# Protection_channel_D_Page_5.net
KiCad netlist of a schematic drawn in Altium Designer
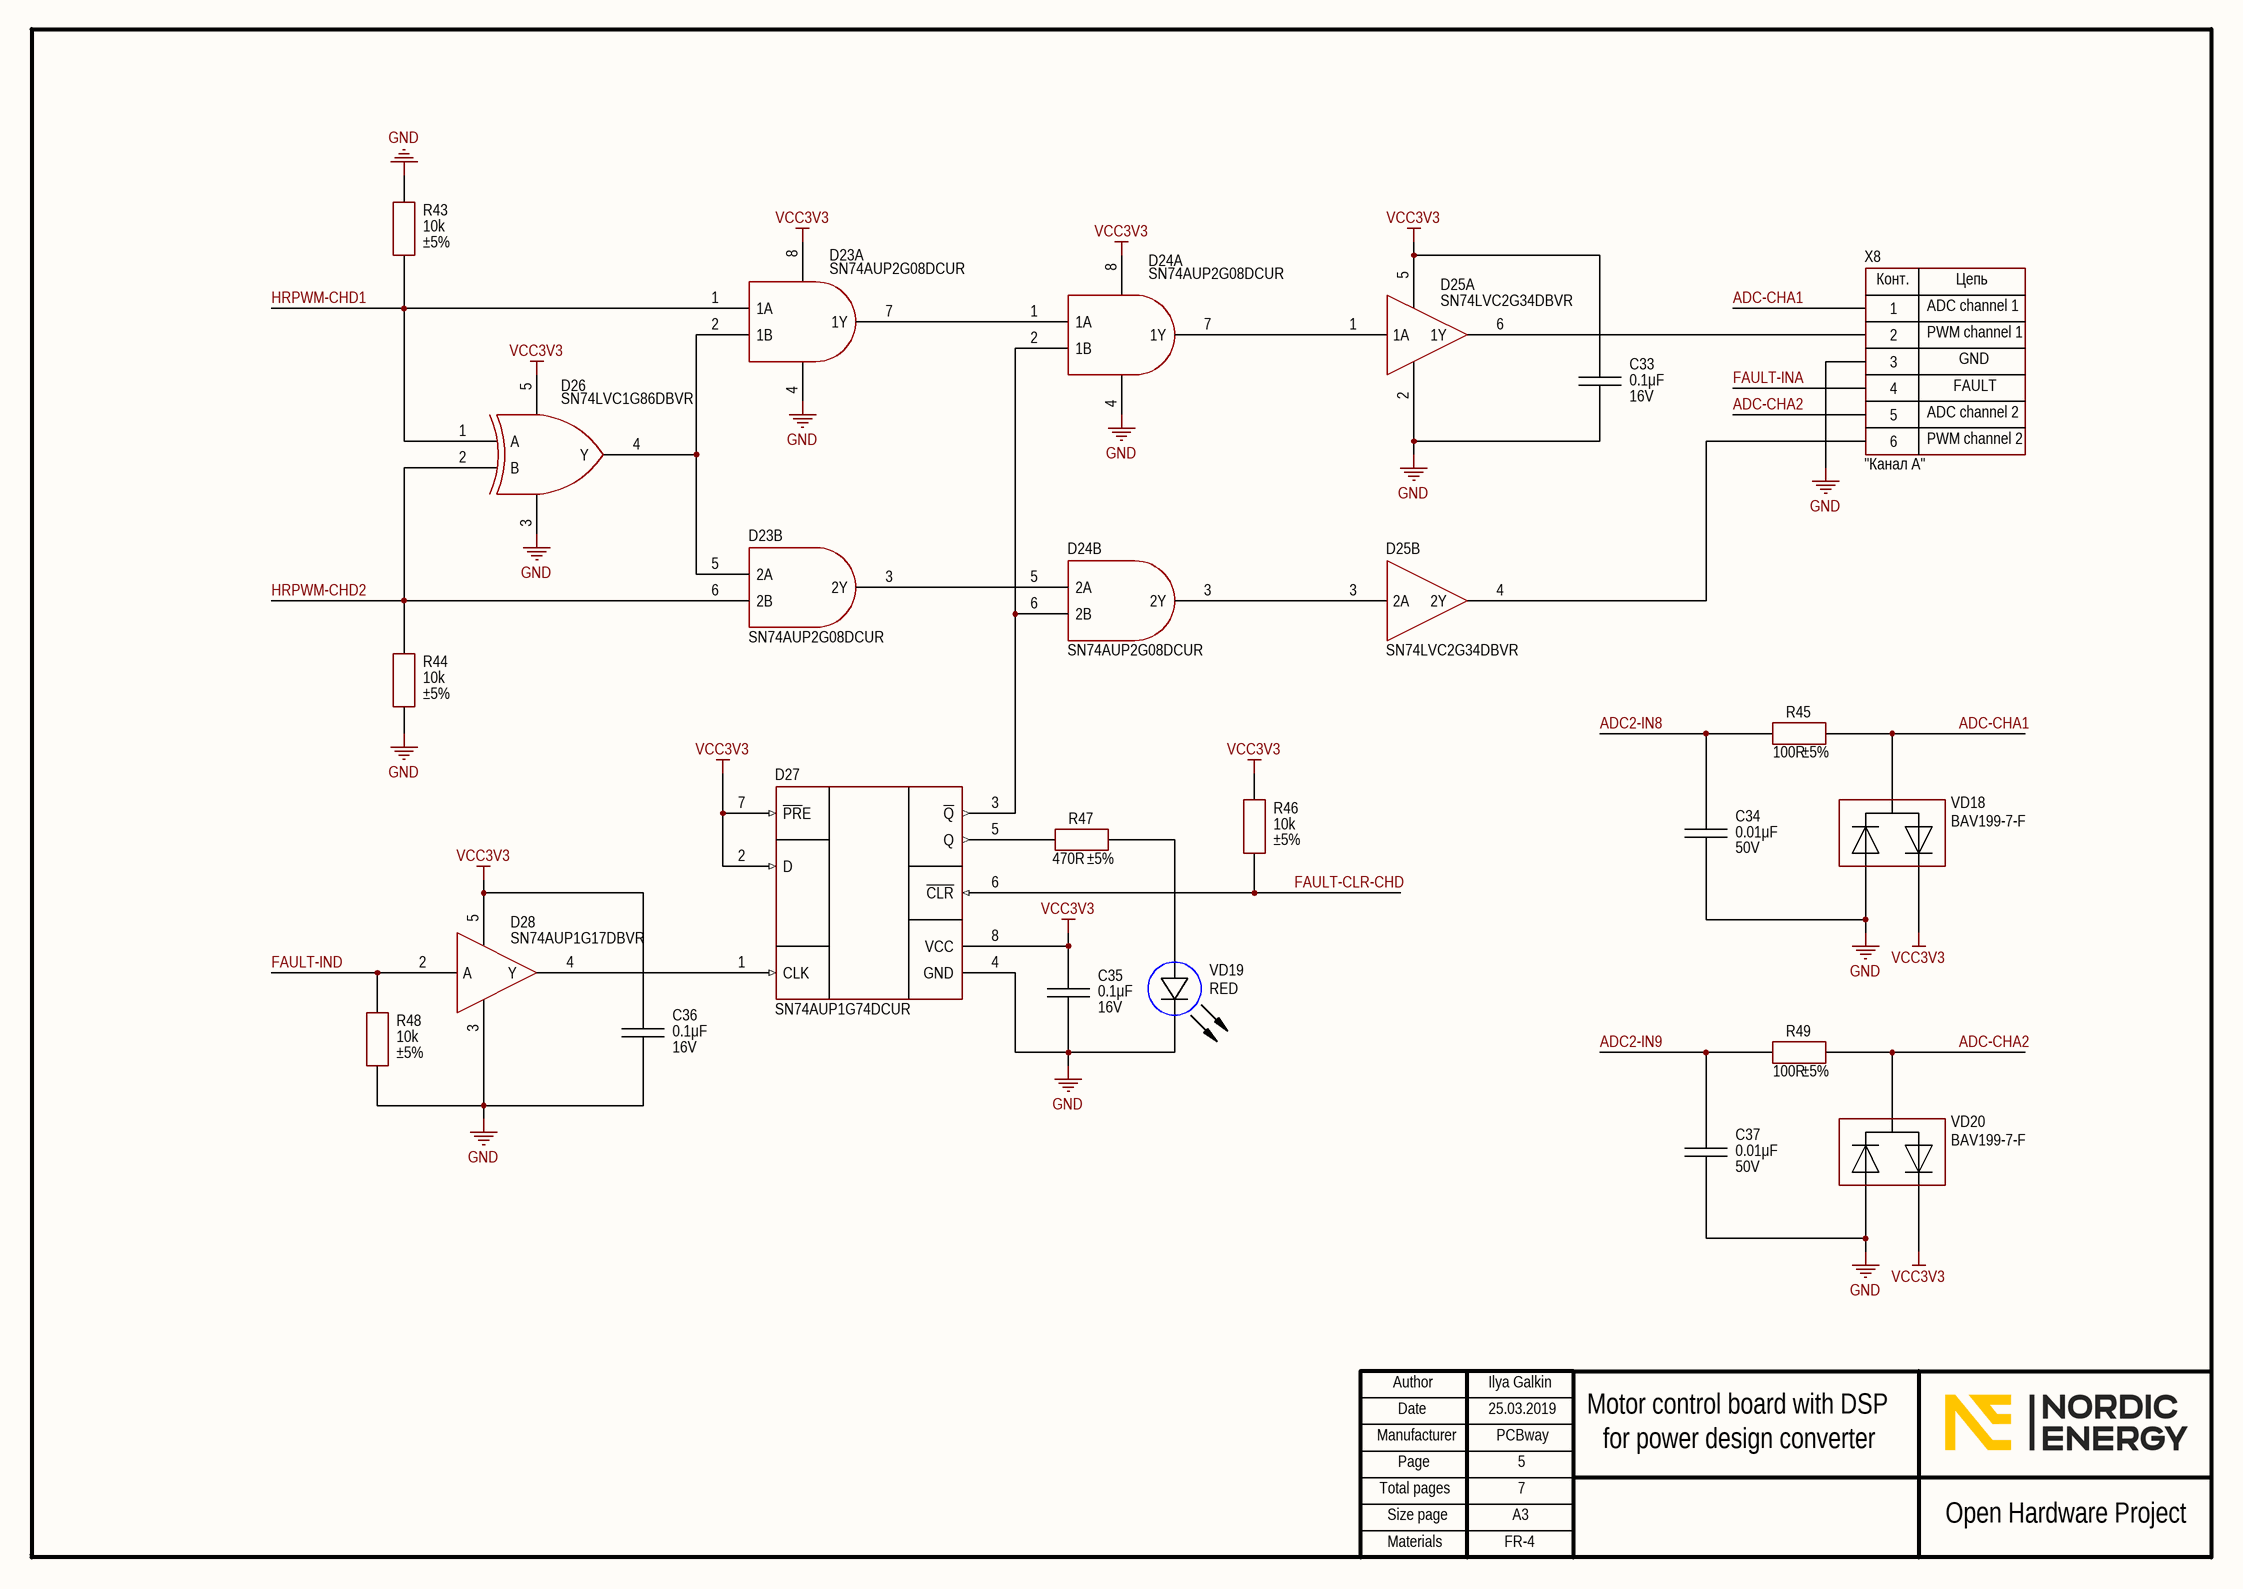
[diagram p0: Protection channel D. Page 5.SchDoc]

(export (version "E")
  (design (tool "Eeschema 10.0.6"))
  (components
    (comp (ref "C33")
      (value "0.1μF")
      (footprint "CAP: 0805")
      (fields
        (field (name "MANUFACTURER") "Yageo")
        (field (name "PARTNUMBER") "CC0805KRX7R7BB104")
        (field (name "VALUEMANUFACTURERPARTNUMBER") "Ceramic capacitor, 0.1μF, X7R, ±10%, 16V, 0805, -55...+125°C")
        (field (name "VOLTAGE") "16V")
      )
      (libsource (lib "Capacitor") (part "Ceramic_0805"))
    )
    (comp (ref "C34")
      (value "0.01μF")
      (footprint "CAP: 0805")
      (fields
        (field (name "MANUFACTURER") "Yageo")
        (field (name "PARTNUMBER") "CC0805KRX7R9BB103")
        (field (name "VALUEMANUFACTURERPARTNUMBER") "Ceramic capacitor, 0.01μF, X7R, ±10%, 50V, 0805, -55...+125°C")
        (field (name "VOLTAGE") "50V")
      )
      (libsource (lib "Capacitor") (part "Ceramic_0805"))
    )
    (comp (ref "C35")
      (value "0.1μF")
      (footprint "CAP: 0805")
      (fields
        (field (name "MANUFACTURER") "Yageo")
        (field (name "PARTNUMBER") "CC0805KRX7R7BB104")
        (field (name "VALUEMANUFACTURERPARTNUMBER") "Ceramic capacitor, 0.1μF, X7R, ±10%, 16V, 0805, -55...+125°C")
        (field (name "VOLTAGE") "16V")
      )
      (libsource (lib "Capacitor") (part "Ceramic_0805"))
    )
    (comp (ref "C36")
      (value "0.1μF")
      (footprint "CAP: 0805")
      (fields
        (field (name "MANUFACTURER") "Yageo")
        (field (name "PARTNUMBER") "CC0805KRX7R7BB104")
        (field (name "VALUEMANUFACTURERPARTNUMBER") "Ceramic capacitor, 0.1μF, X7R, ±10%, 16V, 0805, -55...+125°C")
        (field (name "VOLTAGE") "16V")
      )
      (libsource (lib "Capacitor") (part "Ceramic_0805"))
    )
    (comp (ref "C37")
      (value "0.01μF")
      (footprint "CAP: 0805")
      (fields
        (field (name "MANUFACTURER") "Yageo")
        (field (name "PARTNUMBER") "CC0805KRX7R9BB103")
        (field (name "VALUEMANUFACTURERPARTNUMBER") "Ceramic capacitor, 0.01μF, X7R, ±10%, 50V, 0805, -55...+125°C")
        (field (name "VOLTAGE") "50V")
      )
      (libsource (lib "Capacitor") (part "Ceramic_0805"))
    )
    (comp (ref "D23")
      (value "~")
      (footprint "8-VSSOP")
      (description "AND")
      (fields
        (field (name "MANUFACTURER") "Texas Instruments")
        (field (name "VALUEMANUFACTURERPARTNUMBER") "IC logic AND, 0.8...3.6V, -40...+855°C, 8-VSSOP")
        (field (name "PARTNUMBER") "SN74AUP2G08DCUR")
      )
      (libsource (lib "IC. Logic") (part "SN74AUP2G08DCUR"))
    )
    (comp (ref "D24")
      (value "~")
      (footprint "8-VSSOP")
      (description "AND")
      (fields
        (field (name "MANUFACTURER") "Texas Instruments")
        (field (name "VALUEMANUFACTURERPARTNUMBER") "IC logic AND, 0.8...3.6V, -40...+855°C, 8-VSSOP")
        (field (name "PARTNUMBER") "SN74AUP2G08DCUR")
      )
      (libsource (lib "IC. Logic") (part "SN74AUP2G08DCUR"))
    )
    (comp (ref "D25")
      (value "~")
      (footprint "SOT23-6")
      (description "Buffer")
      (fields
        (field (name "MANUFACTURER") "Texas Instruments")
        (field (name "VALUEMANUFACTURERPARTNUMBER") "IC logic buffer, 1.65...5.5V, -40...+125°C, SOT23-6")
        (field (name "PARTNUMBER") "SN74LVC2G34DBVR")
      )
      (libsource (lib "IC. Logic") (part "SN74LVC2G34DBVR"))
    )
    (comp (ref "D26")
      (value "~")
      (footprint "SOT23-5")
      (description "XOR")
      (fields
        (field (name "MANUFACTURER") "Texas Instruments")
        (field (name "VALUEMANUFACTURERPARTNUMBER") "IC logic XOR, 1.65...5.5V, -40...+125°C, SOT23-5")
        (field (name "PARTNUMBER") "SN74LVC1G86DBVR")
      )
      (libsource (lib "IC. Logic") (part "SN74LVC1G86DBVR"))
    )
    (comp (ref "D27")
      (value "~")
      (footprint "8-VSSOP")
      (description "D-trigger")
      (fields
        (field (name "MANUFACTURER") "Texas Instruments")
        (field (name "VALUEMANUFACTURERPARTNUMBER") "ICtrigger D-type, 0.8...3.6V, -40...+85°C, 8-VSSOP")
        (field (name "PARTNUMBER") "SN74AUP1G74DCUR")
      )
      (libsource (lib "IC. Logic") (part "SN74AUP1G74DCUR"))
    )
    (comp (ref "D28")
      (value "~")
      (footprint "SOT23-5")
      (description "Schmitt trigger")
      (fields
        (field (name "MANUFACTURER") "Texas Instruments")
        (field (name "VALUEMANUFACTURERPARTNUMBER") "IC Schmitt trigger, 0.8...3.6V, -40...+85°C, SOT23-6")
        (field (name "PARTNUMBER") "SN74AUP1G17DBVR")
      )
      (libsource (lib "IC. Logic") (part "SN74AUP1G17DBVR"))
    )
    (comp (ref "R43")
      (value "10k")
      (footprint "RES: 0805")
      (fields
        (field (name "MANUFACTURER") "Yageo")
        (field (name "PARTNUMBER") "RC0805JR-0710KL")
        (field (name "VALUEMANUFACTURERPARTNUMBER") "Resistor film, 10k, ±5%, 0805, 0.125W, -55...+125°C")
        (field (name "TOLERANCE") "±5%")
      )
      (libsource (lib "Resistor") (part "Resistor_0805"))
    )
    (comp (ref "R44")
      (value "10k")
      (footprint "RES: 0805")
      (fields
        (field (name "MANUFACTURER") "Yageo")
        (field (name "PARTNUMBER") "RC0805JR-0710KL")
        (field (name "VALUEMANUFACTURERPARTNUMBER") "Resistor film, 10k, ±5%, 0805, 0.125W, -55...+125°C")
        (field (name "TOLERANCE") "±5%")
      )
      (libsource (lib "Resistor") (part "Resistor_0805"))
    )
    (comp (ref "R45")
      (value "100R")
      (footprint "RES: 0805")
      (fields
        (field (name "MANUFACTURER") "Yageo")
        (field (name "PARTNUMBER") "RC0805JR-07100RL")
        (field (name "VALUEMANUFACTURERPARTNUMBER") "Resistor film, 100R, ±5%, 0805, 0.125W, -55...+125°C")
        (field (name "TOLERANCE") "±5%")
      )
      (libsource (lib "") (part "Resistor_0805_1"))
    )
    (comp (ref "R46")
      (value "10k")
      (footprint "RES: 0805")
      (fields
        (field (name "MANUFACTURER") "Yageo")
        (field (name "PARTNUMBER") "RC0805JR-0710KL")
        (field (name "VALUEMANUFACTURERPARTNUMBER") "Resistor film, 10k, ±5%, 0805, 0.125W, -55...+125°C")
        (field (name "TOLERANCE") "±5%")
      )
      (libsource (lib "Resistor") (part "Resistor_0805"))
    )
    (comp (ref "R47")
      (value "470R")
      (footprint "RES: 0805")
      (fields
        (field (name "MANUFACTURER") "Yageo")
        (field (name "PARTNUMBER") "RC0805JR-07470RL")
        (field (name "VALUEMANUFACTURERPARTNUMBER") "Resistor film, 470R, ±5%, 0805, 0.125W, -55...+125°C")
        (field (name "TOLERANCE") "±5%")
      )
      (libsource (lib "") (part "Resistor_0805_2"))
    )
    (comp (ref "R48")
      (value "10k")
      (footprint "RES: 0805")
      (fields
        (field (name "MANUFACTURER") "Yageo")
        (field (name "PARTNUMBER") "RC0805JR-0710KL")
        (field (name "VALUEMANUFACTURERPARTNUMBER") "Resistor film, 10k, ±5%, 0805, 0.125W, -55...+125°C")
        (field (name "TOLERANCE") "±5%")
      )
      (libsource (lib "Resistor") (part "Resistor_0805"))
    )
    (comp (ref "R49")
      (value "100R")
      (footprint "RES: 0805")
      (fields
        (field (name "MANUFACTURER") "Yageo")
        (field (name "PARTNUMBER") "RC0805JR-07100RL")
        (field (name "VALUEMANUFACTURERPARTNUMBER") "Resistor film, 100R, ±5%, 0805, 0.125W, -55...+125°C")
        (field (name "TOLERANCE") "±5%")
      )
      (libsource (lib "") (part "Resistor_0805_1"))
    )
    (comp (ref "VD18")
      (value "~")
      (footprint "SOT23")
      (fields
        (field (name "MANUFACTURER") "Diodes Incorporated")
        (field (name "VALUEMANUFACTURERPARTNUMBER") "Diode array, 85V, 140mA, 1.1V, 3us, SOT-23, -65...+150°C")
        (field (name "VOLTAGE") "85V")
        (field (name "PARTNUMBER") "BAV199-7-F")
      )
      (libsource (lib "Diode") (part "Diode_array"))
    )
    (comp (ref "VD19")
      (value "~")
      (footprint "LED: 0805R")
      (fields
        (field (name "MANUFACTURER") "Wurth")
        (field (name "VALUEMANUFACTURERPARTNUMBER") "LED, 20mA, 2V, 0805, -55...+150°C")
        (field (name "PARTNUMBER") "150080RS75000")
        (field (name "COLOR") "RED")
      )
      (libsource (lib "Diode") (part "LED_single"))
    )
    (comp (ref "VD20")
      (value "~")
      (footprint "SOT23")
      (fields
        (field (name "MANUFACTURER") "Diodes Incorporated")
        (field (name "VALUEMANUFACTURERPARTNUMBER") "Diode array, 85V, 140mA, 1.1V, 3us, SOT-23, -65...+150°C")
        (field (name "VOLTAGE") "85V")
        (field (name "PARTNUMBER") "BAV199-7-F")
      )
      (libsource (lib "Diode") (part "Diode_array"))
    )
    (comp (ref "X8")
      (value "~")
      (footprint "CON: PLD-6")
      (fields
        (field (name "MANUFACTURER") "Connfly")
        (field (name "VALUEMANUFACTURERPARTNUMBER") "Connector, 6pin, 2.54mm, 500VAC, 3A")
        (field (name "PARTNUMBER") "PLD-6")
        (field (name "COMMENTTEXT") "\"Канал А\"")
      )
      (libsource (lib "Connector") (part "PLD-6"))
    )
  )
  (nets
    (net (code "1") (name "/ADC-CHA1") (class "Default")
      (node (ref "R45") (pin "2") (pinfunction "2_2") (pintype "passive"))
      (node (ref "VD18") (pin "3") (pinfunction "3_3") (pintype "passive"))
      (node (ref "X8") (pin "1") (pinfunction "1_1") (pintype "passive"))
    )
    (net (code "2") (name "/ADC-CHA2") (class "Default")
      (node (ref "R49") (pin "2") (pinfunction "2_2") (pintype "passive"))
      (node (ref "VD20") (pin "3") (pinfunction "3_3") (pintype "passive"))
      (node (ref "X8") (pin "5") (pinfunction "5_5") (pintype "power_in"))
    )
    (net (code "3") (name "/ADC2-IN8") (class "Default")
      (node (ref "C34") (pin "2") (pinfunction "2_2") (pintype "power_in"))
      (node (ref "R45") (pin "1") (pinfunction "1_1") (pintype "passive"))
    )
    (net (code "4") (name "/ADC2-IN9") (class "Default")
      (node (ref "C37") (pin "2") (pinfunction "2_2") (pintype "power_in"))
      (node (ref "R49") (pin "1") (pinfunction "1_1") (pintype "passive"))
    )
    (net (code "5") (name "/FAULT-CLR-CHD") (class "Default")
      (node (ref "D27") (pin "6") (pinfunction "~{CLR}_6") (pintype "input"))
      (node (ref "R46") (pin "2") (pinfunction "2_2") (pintype "passive"))
    )
    (net (code "6") (name "/FAULT-INA") (class "Default")
      (node (ref "X8") (pin "4") (pinfunction "4_4") (pintype "power_in"))
    )
    (net (code "7") (name "/FAULT-IND") (class "Default")
      (node (ref "D28") (pin "2") (pinfunction "A_2") (pintype "passive"))
      (node (ref "R48") (pin "1") (pinfunction "1_1") (pintype "passive"))
    )
    (net (code "8") (name "/HRPWM-CHD1") (class "Default")
      (node (ref "D23") (pin "1") (pinfunction "1A_1") (pintype "passive"))
      (node (ref "D26") (pin "1") (pinfunction "A_1") (pintype "passive"))
      (node (ref "R43") (pin "2") (pinfunction "2_2") (pintype "passive"))
    )
    (net (code "9") (name "/HRPWM-CHD2") (class "Default")
      (node (ref "D23") (pin "6") (pinfunction "2B_6") (pintype "passive"))
      (node (ref "D26") (pin "2") (pinfunction "B_2") (pintype "passive"))
      (node (ref "R44") (pin "1") (pinfunction "1_1") (pintype "passive"))
    )
    (net (code "10") (name "GND") (class "Default")
      (node (ref "C33") (pin "1") (pinfunction "1_1") (pintype "power_in"))
      (node (ref "C34") (pin "1") (pinfunction "1_1") (pintype "power_in"))
      (node (ref "C35") (pin "1") (pinfunction "1_1") (pintype "power_in"))
      (node (ref "C36") (pin "1") (pinfunction "1_1") (pintype "power_in"))
      (node (ref "C37") (pin "1") (pinfunction "1_1") (pintype "power_in"))
      (node (ref "D23") (pin "4") (pintype "passive"))
      (node (ref "D24") (pin "4") (pintype "passive"))
      (node (ref "D25") (pin "2") (pintype "passive"))
      (node (ref "D26") (pin "3") (pintype "passive"))
      (node (ref "D27") (pin "4") (pinfunction "GND_4") (pintype "passive"))
      (node (ref "D28") (pin "3") (pintype "passive"))
      (node (ref "R43") (pin "1") (pinfunction "1_1") (pintype "passive"))
      (node (ref "R44") (pin "2") (pinfunction "2_2") (pintype "passive"))
      (node (ref "R48") (pin "2") (pinfunction "2_2") (pintype "passive"))
      (node (ref "VD18") (pin "1") (pinfunction "1_1") (pintype "passive"))
      (node (ref "VD19") (pin "2") (pinfunction "C_2") (pintype "passive"))
      (node (ref "VD20") (pin "1") (pinfunction "1_1") (pintype "passive"))
      (node (ref "X8") (pin "3") (pinfunction "3_3") (pintype "power_in"))
    )
    (net (code "11") (name "Net-(D23A-1B)") (class "Default")
      (node (ref "D23") (pin "2") (pinfunction "1B_2") (pintype "passive"))
      (node (ref "D23") (pin "5") (pinfunction "2A_5") (pintype "passive"))
      (node (ref "D26") (pin "4") (pinfunction "Y_4") (pintype "passive"))
    )
    (net (code "12") (name "Net-(D23A-1Y)") (class "Default")
      (node (ref "D23") (pin "7") (pinfunction "1Y_7") (pintype "passive"))
      (node (ref "D24") (pin "1") (pinfunction "1A_1") (pintype "passive"))
    )
    (net (code "13") (name "Net-(D23B-2Y)") (class "Default")
      (node (ref "D23") (pin "3") (pinfunction "2Y_3") (pintype "passive"))
      (node (ref "D24") (pin "5") (pinfunction "2A_5") (pintype "passive"))
    )
    (net (code "14") (name "Net-(D24A-1B)") (class "Default")
      (node (ref "D24") (pin "2") (pinfunction "1B_2") (pintype "passive"))
      (node (ref "D24") (pin "6") (pinfunction "2B_6") (pintype "passive"))
      (node (ref "D27") (pin "3") (pinfunction "~{Q}_3") (pintype "output"))
    )
    (net (code "15") (name "Net-(D24A-1Y)") (class "Default")
      (node (ref "D24") (pin "7") (pinfunction "1Y_7") (pintype "passive"))
      (node (ref "D25") (pin "1") (pinfunction "1A_1") (pintype "passive"))
    )
    (net (code "16") (name "Net-(D24B-2Y)") (class "Default")
      (node (ref "D24") (pin "3") (pinfunction "2Y_3") (pintype "passive"))
      (node (ref "D25") (pin "3") (pinfunction "2A_3") (pintype "passive"))
    )
    (net (code "17") (name "Net-(D25A-1Y)") (class "Default")
      (node (ref "D25") (pin "6") (pinfunction "1Y_6") (pintype "passive"))
      (node (ref "X8") (pin "2") (pinfunction "2_2") (pintype "passive"))
    )
    (net (code "18") (name "Net-(D25B-2Y)") (class "Default")
      (node (ref "D25") (pin "4") (pinfunction "2Y_4") (pintype "passive"))
      (node (ref "X8") (pin "6") (pinfunction "6_6") (pintype "power_in"))
    )
    (net (code "19") (name "Net-(D27-CLK)") (class "Default")
      (node (ref "D27") (pin "1") (pinfunction "CLK_1") (pintype "input"))
      (node (ref "D28") (pin "4") (pinfunction "Y_4") (pintype "passive"))
    )
    (net (code "20") (name "Net-(D27-Q)") (class "Default")
      (node (ref "D27") (pin "5") (pinfunction "Q_5") (pintype "output"))
      (node (ref "R47") (pin "2") (pinfunction "2_2") (pintype "passive"))
    )
    (net (code "21") (name "Net-(VD19-A)") (class "Default")
      (node (ref "R47") (pin "1") (pinfunction "1_1") (pintype "passive"))
      (node (ref "VD19") (pin "1") (pinfunction "A_1") (pintype "passive"))
    )
    (net (code "22") (name "VCC3V3") (class "Default")
      (node (ref "C33") (pin "2") (pinfunction "2_2") (pintype "power_in"))
      (node (ref "C35") (pin "2") (pinfunction "2_2") (pintype "power_in"))
      (node (ref "C36") (pin "2") (pinfunction "2_2") (pintype "power_in"))
      (node (ref "D23") (pin "8") (pintype "passive"))
      (node (ref "D24") (pin "8") (pintype "passive"))
      (node (ref "D25") (pin "5") (pintype "passive"))
      (node (ref "D26") (pin "5") (pintype "passive"))
      (node (ref "D27") (pin "2") (pinfunction "D_2") (pintype "input"))
      (node (ref "D27") (pin "7") (pinfunction "~{PR}E_7") (pintype "input"))
      (node (ref "D27") (pin "8") (pinfunction "VCC_8") (pintype "passive"))
      (node (ref "D28") (pin "5") (pintype "passive"))
      (node (ref "R46") (pin "1") (pinfunction "1_1") (pintype "passive"))
      (node (ref "VD18") (pin "2") (pinfunction "2_2") (pintype "passive"))
      (node (ref "VD20") (pin "2") (pinfunction "2_2") (pintype "passive"))
    )
  )
)
